# LoRa-Bee_v11.net
KiCad netlist of a schematic drawn in EAGLE
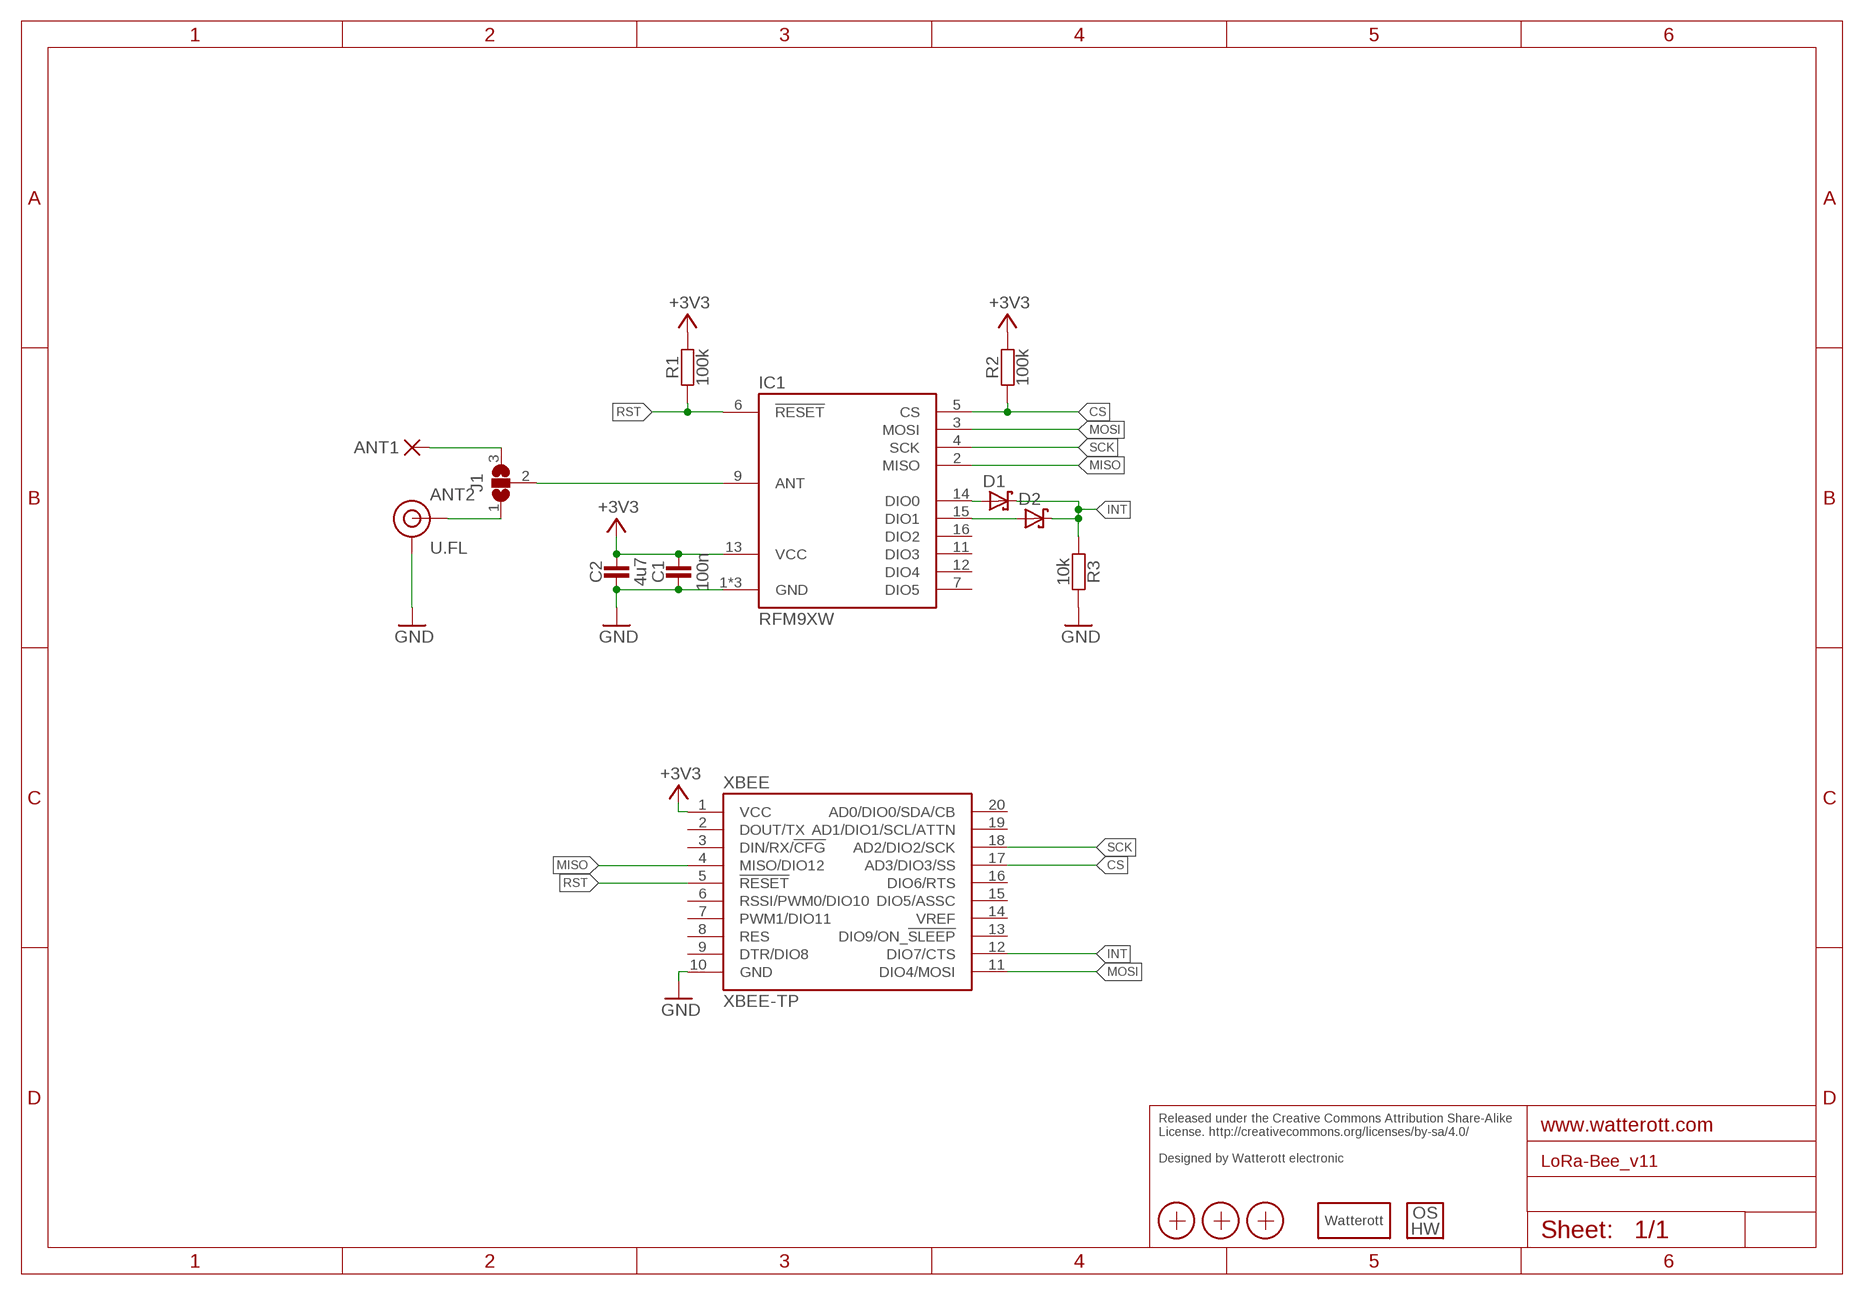
[diagram p0: schematic, sheet 1]

(export (version "E")
  (design (tool "Eeschema 10.0.6"))
  (components
    (comp (ref "ANT1")
      (value "PAD-1.00-1.60")
      (footprint "eagle-import:PAD-1.00-1.60")
      (libsource (lib "eagle-import") (part "PAD-1.00-1.60"))
    )
    (comp (ref "ANT2")
      (value "U.FL")
      (footprint "eagle-import:U.FL")
      (libsource (lib "eagle-import") (part "U.FL"))
    )
    (comp (ref "C1")
      (value "100n")
      (footprint "eagle-import:C0402")
      (libsource (lib "eagle-import") (part "CAPACITOR-0402"))
    )
    (comp (ref "C2")
      (value "4u7")
      (footprint "eagle-import:C0402")
      (libsource (lib "eagle-import") (part "CAPACITOR-0402"))
    )
    (comp (ref "D1")
      (value "D_SCHOTTKY-SOD532")
      (footprint "eagle-import:SOD523")
      (libsource (lib "eagle-import") (part "D_SCHOTTKY-SOD532"))
    )
    (comp (ref "D2")
      (value "D_SCHOTTKY-SOD532")
      (footprint "eagle-import:SOD523")
      (libsource (lib "eagle-import") (part "D_SCHOTTKY-SOD532"))
    )
    (comp (ref "IC1")
      (value "RFM9XW")
      (footprint "eagle-import:RFM9X")
      (libsource (lib "eagle-import") (part "RFM9XW"))
    )
    (comp (ref "J1")
      (value "JUMPER3-0603")
      (footprint "eagle-import:JUMPER3-0603")
      (libsource (lib "eagle-import") (part "JUMPER3-0603"))
    )
    (comp (ref "LOGO3")
      (value "LOGO_SPARK-2")
      (footprint "eagle-import:SPARK_2MM")
      (libsource (lib "eagle-import") (part "LOGO_SPARK-2"))
    )
    (comp (ref "LOGO4")
      (value "LOGO_OSHW-2")
      (footprint "eagle-import:OSHW_2MM")
      (libsource (lib "eagle-import") (part "LOGO_OSHW-2"))
    )
    (comp (ref "R1")
      (value "100k")
      (footprint "eagle-import:C0402")
      (libsource (lib "eagle-import") (part "RESISTOR-0402"))
    )
    (comp (ref "R2")
      (value "100k")
      (footprint "eagle-import:C0402")
      (libsource (lib "eagle-import") (part "RESISTOR-0402"))
    )
    (comp (ref "R3")
      (value "10k")
      (footprint "eagle-import:C0402")
      (libsource (lib "eagle-import") (part "RESISTOR-0402"))
    )
    (comp (ref "X1")
      (value "PASSER-07")
      (footprint "eagle-import:PASSER_07MM")
      (libsource (lib "eagle-import") (part "PASSER-07"))
    )
    (comp (ref "X2")
      (value "PASSER-07")
      (footprint "eagle-import:PASSER_07MM")
      (libsource (lib "eagle-import") (part "PASSER-07"))
    )
    (comp (ref "X3")
      (value "PASSER-07")
      (footprint "eagle-import:PASSER_07MM")
      (libsource (lib "eagle-import") (part "PASSER-07"))
    )
    (comp (ref "XBEE")
      (value "XBEE-TP")
      (footprint "eagle-import:XBEE_TP")
      (libsource (lib "eagle-import") (part "XBEE-TP"))
    )
  )
  (nets
    (net (code "1") (name "+3V3") (class "Default")
      (node (ref "C1") (pin "2") (pinfunction "2_2") (pintype "passive"))
      (node (ref "C2") (pin "2") (pinfunction "2_2") (pintype "passive"))
      (node (ref "IC1") (pin "13") (pinfunction "VCC_13") (pintype "power_in"))
      (node (ref "R1") (pin "2") (pinfunction "2_2") (pintype "passive"))
      (node (ref "R2") (pin "2") (pinfunction "2_2") (pintype "passive"))
      (node (ref "XBEE") (pin "1") (pinfunction "VCC_1") (pintype "power_in"))
    )
    (net (code "2") (name "CS") (class "Default")
      (node (ref "IC1") (pin "5") (pinfunction "CS_5") (pintype "input"))
      (node (ref "R2") (pin "1") (pinfunction "1_1") (pintype "passive"))
      (node (ref "XBEE") (pin "17") (pinfunction "AD3/DIO3/SS_17") (pintype "bidirectional"))
    )
    (net (code "3") (name "GND") (class "Default")
      (node (ref "ANT2") (pin "1") (pinfunction "GND_1") (pintype "bidirectional"))
      (node (ref "ANT2") (pin "2") (pinfunction "GND_2") (pintype "bidirectional"))
      (node (ref "C1") (pin "1") (pinfunction "1_1") (pintype "passive"))
      (node (ref "C2") (pin "1") (pinfunction "1_1") (pintype "passive"))
      (node (ref "IC1") (pin "1") (pinfunction "GND_1") (pintype "power_in"))
      (node (ref "IC1") (pin "10") (pinfunction "GND_10") (pintype "power_in"))
      (node (ref "IC1") (pin "8") (pinfunction "GND_8") (pintype "power_in"))
      (node (ref "R3") (pin "2") (pinfunction "2_2") (pintype "passive"))
      (node (ref "XBEE") (pin "10") (pinfunction "GND_10") (pintype "power_in"))
    )
    (net (code "4") (name "INT") (class "Default")
      (node (ref "D1") (pin "C") (pinfunction "C_C") (pintype "passive"))
      (node (ref "D2") (pin "C") (pinfunction "C_C") (pintype "passive"))
      (node (ref "R3") (pin "1") (pinfunction "1_1") (pintype "passive"))
      (node (ref "XBEE") (pin "12") (pinfunction "DIO7/CTS_12") (pintype "bidirectional"))
    )
    (net (code "5") (name "MISO") (class "Default")
      (node (ref "IC1") (pin "2") (pinfunction "MISO_2") (pintype "output"))
      (node (ref "XBEE") (pin "4") (pinfunction "MISO/DIO12_4") (pintype "bidirectional"))
    )
    (net (code "6") (name "MOSI") (class "Default")
      (node (ref "IC1") (pin "3") (pinfunction "MOSI_3") (pintype "input"))
      (node (ref "XBEE") (pin "11") (pinfunction "DIO4/MOSI_11") (pintype "bidirectional"))
    )
    (net (code "7") (name "Net-(ANT1-P)") (class "Default")
      (node (ref "ANT1") (pin "1") (pinfunction "P_1") (pintype "passive"))
      (node (ref "J1") (pin "3") (pinfunction "3_3") (pintype "passive"))
    )
    (net (code "8") (name "Net-(ANT2-SIGNAL)") (class "Default")
      (node (ref "ANT2") (pin "FEED") (pinfunction "SIGNAL_FEED") (pintype "bidirectional"))
      (node (ref "J1") (pin "1") (pinfunction "1_1") (pintype "passive"))
    )
    (net (code "9") (name "Net-(IC1-ANT)") (class "Default")
      (node (ref "IC1") (pin "9") (pinfunction "ANT_9") (pintype "bidirectional"))
      (node (ref "J1") (pin "2") (pinfunction "2_2") (pintype "passive"))
    )
    (net (code "10") (name "Net-(IC1-DIO0)") (class "Default")
      (node (ref "D1") (pin "A") (pinfunction "A_A") (pintype "passive"))
      (node (ref "IC1") (pin "14") (pinfunction "DIO0_14") (pintype "bidirectional"))
    )
    (net (code "11") (name "Net-(IC1-DIO1)") (class "Default")
      (node (ref "D2") (pin "A") (pinfunction "A_A") (pintype "passive"))
      (node (ref "IC1") (pin "15") (pinfunction "DIO1_15") (pintype "bidirectional"))
    )
    (net (code "12") (name "RST") (class "Default")
      (node (ref "IC1") (pin "6") (pinfunction "~{RESET}_6") (pintype "input"))
      (node (ref "R1") (pin "1") (pinfunction "1_1") (pintype "passive"))
      (node (ref "XBEE") (pin "5") (pinfunction "~{RESET}_5") (pintype "bidirectional"))
    )
    (net (code "13") (name "SCK") (class "Default")
      (node (ref "IC1") (pin "4") (pinfunction "SCK_4") (pintype "input"))
      (node (ref "XBEE") (pin "18") (pinfunction "AD2/DIO2/SCK_18") (pintype "bidirectional"))
    )
    (net (code "14") (name "unconnected-(IC1-DIO2-Pad16)") (class "Default")
      (node (ref "IC1") (pin "16") (pinfunction "DIO2_16") (pintype "bidirectional"))
    )
    (net (code "15") (name "unconnected-(IC1-DIO3-Pad11)") (class "Default")
      (node (ref "IC1") (pin "11") (pinfunction "DIO3_11") (pintype "bidirectional"))
    )
    (net (code "16") (name "unconnected-(IC1-DIO4-Pad12)") (class "Default")
      (node (ref "IC1") (pin "12") (pinfunction "DIO4_12") (pintype "bidirectional"))
    )
    (net (code "17") (name "unconnected-(IC1-DIO5-Pad7)") (class "Default")
      (node (ref "IC1") (pin "7") (pinfunction "DIO5_7") (pintype "bidirectional"))
    )
    (net (code "18") (name "unconnected-(XBEE-AD0{slash}DIO0{slash}SDA{slash}CB-Pad20)") (class "Default")
      (node (ref "XBEE") (pin "20") (pinfunction "AD0/DIO0/SDA/CB_20") (pintype "bidirectional"))
    )
    (net (code "19") (name "unconnected-(XBEE-AD1{slash}DIO1{slash}SCL{slash}ATTN-Pad19)") (class "Default")
      (node (ref "XBEE") (pin "19") (pinfunction "AD1/DIO1/SCL/ATTN_19") (pintype "bidirectional"))
    )
    (net (code "20") (name "unconnected-(XBEE-DIN{slash}RX{slash}~{CFG}-Pad3)") (class "Default")
      (node (ref "XBEE") (pin "3") (pinfunction "DIN/RX/~{CFG}_3") (pintype "bidirectional"))
    )
    (net (code "21") (name "unconnected-(XBEE-DIO5{slash}ASSC-Pad15)") (class "Default")
      (node (ref "XBEE") (pin "15") (pinfunction "DIO5/ASSC_15") (pintype "bidirectional"))
    )
    (net (code "22") (name "unconnected-(XBEE-DIO6{slash}RTS-Pad16)") (class "Default")
      (node (ref "XBEE") (pin "16") (pinfunction "DIO6/RTS_16") (pintype "bidirectional"))
    )
    (net (code "23") (name "unconnected-(XBEE-DIO9{slash}ON_~{SLEEP}-Pad13)") (class "Default")
      (node (ref "XBEE") (pin "13") (pinfunction "DIO9/ON_~{SLEEP}_13") (pintype "bidirectional"))
    )
    (net (code "24") (name "unconnected-(XBEE-DOUT{slash}TX-Pad2)") (class "Default")
      (node (ref "XBEE") (pin "2") (pinfunction "DOUT/TX_2") (pintype "bidirectional"))
    )
    (net (code "25") (name "unconnected-(XBEE-DTR{slash}DIO8-Pad9)") (class "Default")
      (node (ref "XBEE") (pin "9") (pinfunction "DTR/DIO8_9") (pintype "bidirectional"))
    )
    (net (code "26") (name "unconnected-(XBEE-PWM1{slash}DIO11-Pad7)") (class "Default")
      (node (ref "XBEE") (pin "7") (pinfunction "PWM1/DIO11_7") (pintype "bidirectional"))
    )
    (net (code "27") (name "unconnected-(XBEE-RES-Pad8)") (class "Default")
      (node (ref "XBEE") (pin "8") (pinfunction "RES_8") (pintype "bidirectional"))
    )
    (net (code "28") (name "unconnected-(XBEE-RSSI{slash}PWM0{slash}DIO10-Pad6)") (class "Default")
      (node (ref "XBEE") (pin "6") (pinfunction "RSSI/PWM0/DIO10_6") (pintype "bidirectional"))
    )
    (net (code "29") (name "unconnected-(XBEE-VREF-Pad14)") (class "Default")
      (node (ref "XBEE") (pin "14") (pinfunction "VREF_14") (pintype "bidirectional"))
    )
  )
)
